# schematic.net
KiCad netlist of a schematic drawn in EasyEDA Pro
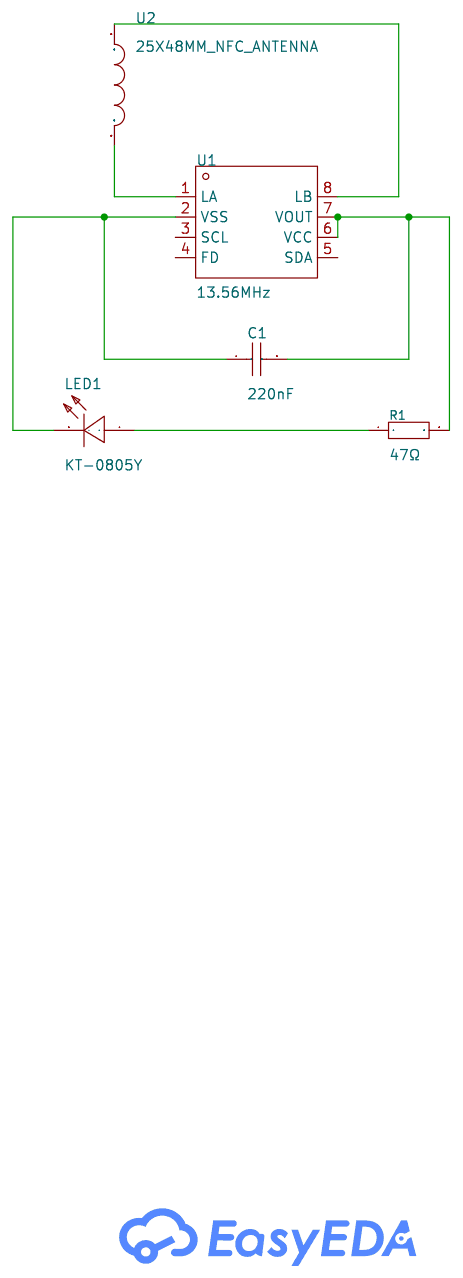
[diagram p0: schematic sheet]

(export (version "E")
  (design (tool "Eeschema 10.0.6"))
  (components
    (comp (ref "C1")
      (value "220nF")
      (footprint "easyedapro:C0603")
      (fields
        (field (name "Manufacturer Part") "CL10B224KA8NNNC")
        (field (name "Manufacturer") "SAMSUNG(三星)")
      )
      (libsource (lib "easyedapro") (part "CL10B224KA8NNNC"))
    )
    (comp (ref "LED1")
      (value "KT-0805Y")
      (footprint "easyedapro:LED0805-R-RD")
      (fields (field (name "Manufacturer") "KENTO"))
      (libsource (lib "easyedapro") (part "17-21SUYC/TR8"))
    )
    (comp (ref "R1")
      (value "47Ω")
      (footprint "easyedapro:R0603")
      (fields
        (field (name "Manufacturer Part") "0603WAF470JT5E")
        (field (name "Manufacturer") "UNI-ROYAL(厚声)")
      )
      (libsource (lib "easyedapro") (part "0603WAF470JT5E"))
    )
    (comp (ref "U1")
      (value "13.56MHz")
      (footprint "easyedapro:XQFN-8_L1.6-W1.6-P0.50-BL_NT3H2111W0FHKH")
      (fields (field (name "Manufacturer Part") "NT3H2111W0FHKH") (field (name "Manufacturer") "NXP(恩智浦)"))
      (libsource (lib "easyedapro") (part "NT3H2111W0FHKH"))
    )
    (comp (ref "U2")
      (value "25X48MM_NFC_ANTENNA")
      (footprint "easyedapro:25X48MM_NFC_ANTENNA")
      (libsource (lib "easyedapro") (part "25X48MM_NFC_ANTENNA"))
    )
  )
  (nets
    (net (code "1") (name "Net-(LED1-+)") (class "Default")
      (node (ref "LED1") (pin "1") (pinfunction "+_1") (pintype "unspecified"))
      (node (ref "R1") (pin "1") (pinfunction "1_1") (pintype "input"))
    )
    (net (code "2") (name "Net-(LED1--)") (class "Default")
      (node (ref "C1") (pin "1") (pinfunction "1_1") (pintype "input"))
      (node (ref "LED1") (pin "2") (pinfunction "-_2") (pintype "unspecified"))
      (node (ref "U1") (pin "2") (pinfunction "VSS_2") (pintype "unspecified"))
    )
    (net (code "3") (name "Net-(U1-LA)") (class "Default")
      (node (ref "U1") (pin "1") (pinfunction "LA_1") (pintype "unspecified"))
      (node (ref "U2") (pin "P$2") (pinfunction "P$2_P$2") (pintype "bidirectional"))
    )
    (net (code "4") (name "Net-(U1-LB)") (class "Default")
      (node (ref "U1") (pin "8") (pinfunction "LB_8") (pintype "unspecified"))
      (node (ref "U2") (pin "P$1") (pinfunction "P$1_P$1") (pintype "bidirectional"))
    )
    (net (code "5") (name "Net-(U1-VCC)") (class "Default")
      (node (ref "C1") (pin "2") (pinfunction "2_2") (pintype "input"))
      (node (ref "R1") (pin "2") (pinfunction "2_2") (pintype "input"))
      (node (ref "U1") (pin "6") (pinfunction "VCC_6") (pintype "unspecified"))
      (node (ref "U1") (pin "7") (pinfunction "VOUT_7") (pintype "unspecified"))
    )
    (net (code "6") (name "unconnected-(U1-FD-Pad4)") (class "Default")
      (node (ref "U1") (pin "4") (pinfunction "FD_4") (pintype "unspecified"))
    )
    (net (code "7") (name "unconnected-(U1-SCL-Pad3)") (class "Default")
      (node (ref "U1") (pin "3") (pinfunction "SCL_3") (pintype "unspecified"))
    )
    (net (code "8") (name "unconnected-(U1-SDA-Pad5)") (class "Default")
      (node (ref "U1") (pin "5") (pinfunction "SDA_5") (pintype "unspecified"))
    )
  )
)
